# 03_ANALOG_A.net
KiCad netlist of a schematic drawn in Altium Designer
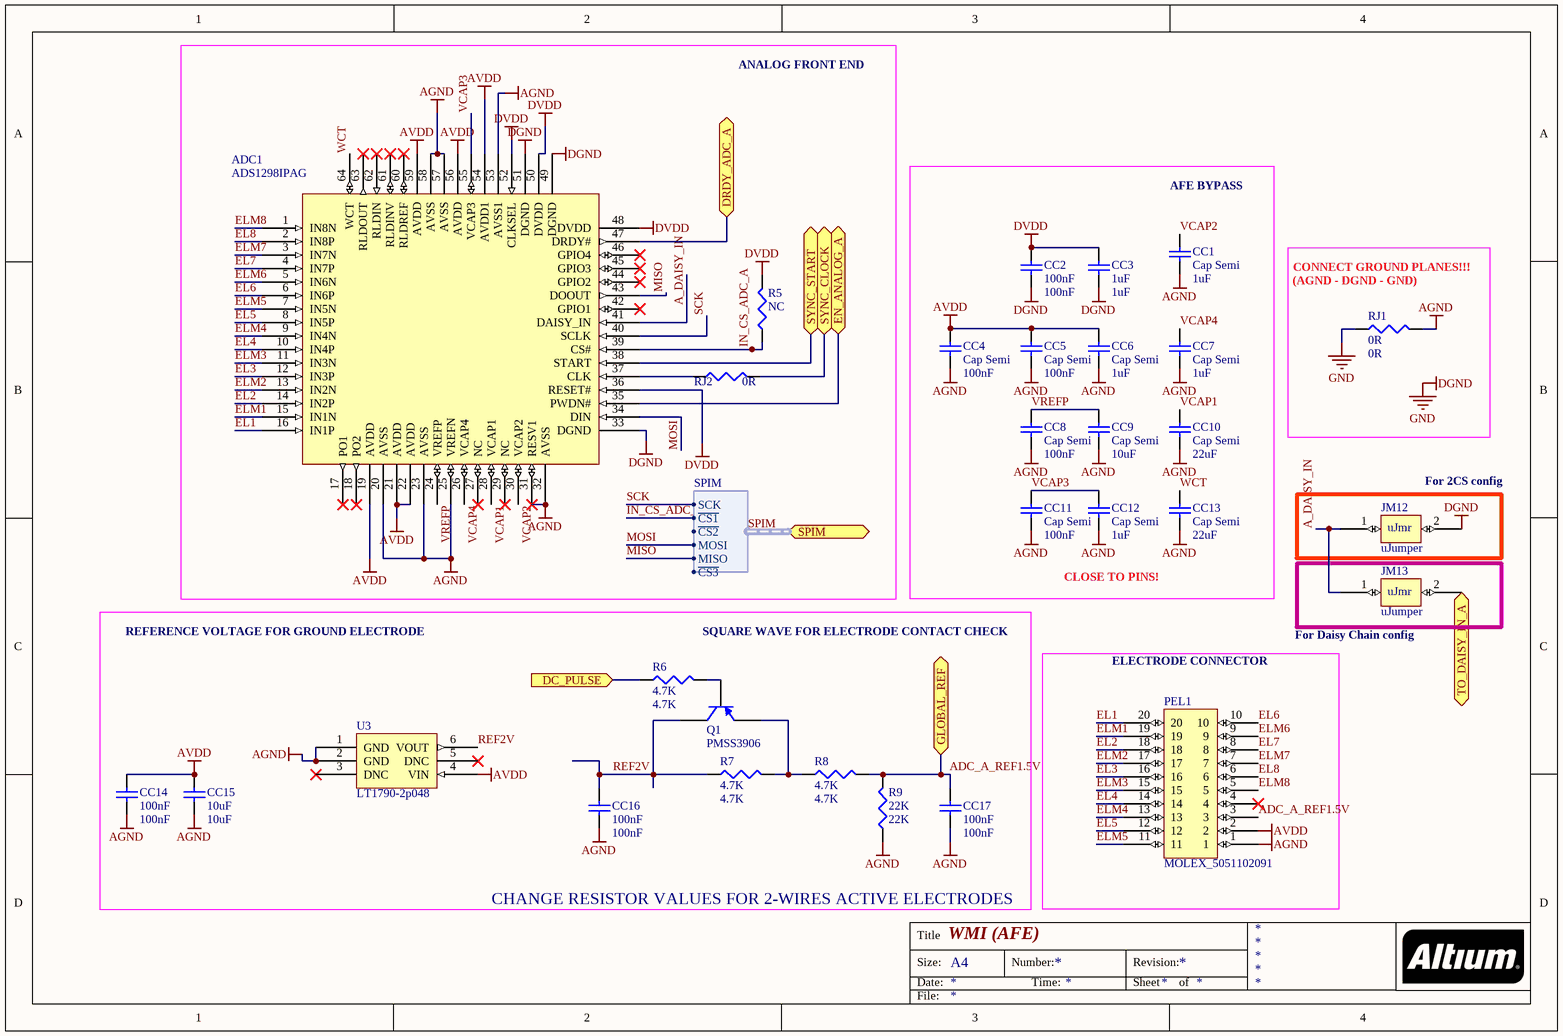
[diagram p0: 03_ANALOG_A.SchDoc]

(export (version "E")
  (design (tool "Eeschema 10.0.6"))
  (components
    (comp (ref "ADC1")
      (value "ADS1298IPAG")
      (footprint "Atmel Microcontroller 32-Bit ARM:LQFP64_M")
      (libsource (lib "Schlib1") (part "ADS1298"))
    )
    (comp (ref "CC1")
      (value "Cap Semi")
      (footprint "0402")
      (description "Capacitor (Semiconductor SIM Model)")
      (fields (field (name "ALTIUM_VALUE") "1uF") (field (name "PUBLISHER") "Altium Limited"))
      (libsource (lib "Miscellaneous Devices") (part "Cap Semi"))
    )
    (comp (ref "CC2")
      (value "100nF")
      (footprint "0402")
      (description "Capacitor (Semiconductor SIM Model)")
      (fields (field (name "ALTIUM_VALUE") "100nF") (field (name "PUBLISHER") "Altium Limited"))
      (libsource (lib "Miscellaneous Devices") (part "Cap Semi"))
    )
    (comp (ref "CC3")
      (value "1uF")
      (footprint "0402")
      (description "Capacitor (Semiconductor SIM Model)")
      (fields (field (name "ALTIUM_VALUE") "1uF") (field (name "PUBLISHER") "Altium Limited"))
      (libsource (lib "Miscellaneous Devices") (part "Cap Semi"))
    )
    (comp (ref "CC4")
      (value "Cap Semi")
      (footprint "0402")
      (description "Capacitor (Semiconductor SIM Model)")
      (fields (field (name "ALTIUM_VALUE") "100nF") (field (name "PUBLISHER") "Altium Limited"))
      (libsource (lib "Miscellaneous Devices") (part "Cap Semi"))
    )
    (comp (ref "CC5")
      (value "Cap Semi")
      (footprint "0402")
      (description "Capacitor (Semiconductor SIM Model)")
      (fields (field (name "ALTIUM_VALUE") "100nF") (field (name "PUBLISHER") "Altium Limited"))
      (libsource (lib "Miscellaneous Devices") (part "Cap Semi"))
    )
    (comp (ref "CC6")
      (value "Cap Semi")
      (footprint "0402")
      (description "Capacitor (Semiconductor SIM Model)")
      (fields (field (name "ALTIUM_VALUE") "1uF") (field (name "PUBLISHER") "Altium Limited"))
      (libsource (lib "Miscellaneous Devices") (part "Cap Semi"))
    )
    (comp (ref "CC7")
      (value "Cap Semi")
      (footprint "0402")
      (description "Capacitor (Semiconductor SIM Model)")
      (fields (field (name "ALTIUM_VALUE") "1uF") (field (name "PUBLISHER") "Altium Limited"))
      (libsource (lib "Miscellaneous Devices") (part "Cap Semi"))
    )
    (comp (ref "CC8")
      (value "Cap Semi")
      (footprint "0402")
      (description "Capacitor (Semiconductor SIM Model)")
      (fields (field (name "ALTIUM_VALUE") "100nF") (field (name "PUBLISHER") "Altium Limited"))
      (libsource (lib "Miscellaneous Devices") (part "Cap Semi"))
    )
    (comp (ref "CC9")
      (value "Cap Semi")
      (footprint "0402")
      (description "Capacitor (Semiconductor SIM Model)")
      (fields (field (name "ALTIUM_VALUE") "10uF") (field (name "PUBLISHER") "Altium Limited"))
      (libsource (lib "Miscellaneous Devices") (part "Cap Semi"))
    )
    (comp (ref "CC10")
      (value "Cap Semi")
      (footprint "J1-0603")
      (description "Capacitor (Semiconductor SIM Model)")
      (fields (field (name "ALTIUM_VALUE") "22uF") (field (name "PUBLISHER") "Altium Limited"))
      (libsource (lib "Miscellaneous Devices") (part "Cap Semi"))
    )
    (comp (ref "CC11")
      (value "Cap Semi")
      (footprint "0402")
      (description "Capacitor (Semiconductor SIM Model)")
      (fields (field (name "ALTIUM_VALUE") "100nF") (field (name "PUBLISHER") "Altium Limited"))
      (libsource (lib "Miscellaneous Devices") (part "Cap Semi"))
    )
    (comp (ref "CC12")
      (value "Cap Semi")
      (footprint "0402")
      (description "Capacitor (Semiconductor SIM Model)")
      (fields (field (name "ALTIUM_VALUE") "1uF") (field (name "PUBLISHER") "Altium Limited"))
      (libsource (lib "Miscellaneous Devices") (part "Cap Semi"))
    )
    (comp (ref "CC13")
      (value "Cap Semi")
      (footprint "1608[0603]")
      (description "Capacitor (Semiconductor SIM Model)")
      (fields (field (name "ALTIUM_VALUE") "22uF") (field (name "PUBLISHER") "Altium Limited"))
      (libsource (lib "Miscellaneous Devices") (part "Cap Semi"))
    )
    (comp (ref "CC14")
      (value "100nF")
      (footprint "0402")
      (description "Capacitor (Semiconductor SIM Model)")
      (fields (field (name "ALTIUM_VALUE") "100nF") (field (name "PUBLISHER") "Altium Limited"))
      (libsource (lib "Miscellaneous Devices") (part "Cap Semi"))
    )
    (comp (ref "CC15")
      (value "10uF")
      (footprint "0402")
      (description "Capacitor (Semiconductor SIM Model)")
      (fields (field (name "ALTIUM_VALUE") "10uF") (field (name "PUBLISHER") "Altium Limited"))
      (libsource (lib "Miscellaneous Devices") (part "Cap Semi"))
    )
    (comp (ref "CC16")
      (value "100nF")
      (footprint "0402")
      (description "Capacitor (Semiconductor SIM Model)")
      (fields (field (name "ALTIUM_VALUE") "100nF") (field (name "PUBLISHER") "Altium Limited"))
      (libsource (lib "Miscellaneous Devices") (part "Cap Semi"))
    )
    (comp (ref "CC17")
      (value "100nF")
      (footprint "0402")
      (description "Capacitor (Semiconductor SIM Model)")
      (fields (field (name "ALTIUM_VALUE") "100nF") (field (name "PUBLISHER") "Altium Limited"))
      (libsource (lib "Miscellaneous Devices") (part "Cap Semi"))
    )
    (comp (ref "JM12") (value "uJumper") (footprint "UJMPR") (libsource (lib "Schlib1") (part "uJumper")))
    (comp (ref "JM13") (value "uJumper") (footprint "UJMPR") (libsource (lib "Schlib1") (part "uJumper")))
    (comp (ref "PEL1")
      (value "MOLEX_5051102091")
      (footprint "MOLEX_5051102091")
      (libsource (lib "Schlib1") (part "MOLEX_5051102091"))
    )
    (comp (ref "Q1")
      (value "PMSS3906")
      (footprint "SOT323_N")
      (description "PNP Switching Transistor")
      (fields (field (name "PUBLISHER") "Altium Limited"))
      (libsource (lib "Philips Discrete BJT - Low Power") (part "PMSS3906"))
    )
    (comp (ref "R5")
      (value "NC")
      (footprint "0402")
      (description "Resistor")
      (fields (field (name "PUBLISHER") "Altium Limited"))
      (libsource (lib "Miscellaneous Devices") (part "Res3"))
    )
    (comp (ref "R6")
      (value "4.7K")
      (footprint "0402")
      (description "Resistor")
      (fields (field (name "ALTIUM_VALUE") "4.7K") (field (name "PUBLISHER") "Altium Limited"))
      (libsource (lib "Miscellaneous Devices") (part "Res3"))
    )
    (comp (ref "R7")
      (value "4.7K")
      (footprint "0402")
      (description "Resistor")
      (fields (field (name "ALTIUM_VALUE") "4.7K") (field (name "PUBLISHER") "Altium Limited"))
      (libsource (lib "Miscellaneous Devices") (part "Res3"))
    )
    (comp (ref "R8")
      (value "4.7K")
      (footprint "0402")
      (description "Resistor")
      (fields (field (name "ALTIUM_VALUE") "4.7K") (field (name "PUBLISHER") "Altium Limited"))
      (libsource (lib "Miscellaneous Devices") (part "Res3"))
    )
    (comp (ref "R9")
      (value "22K")
      (footprint "0402")
      (description "Resistor")
      (fields (field (name "ALTIUM_VALUE") "22K") (field (name "PUBLISHER") "Altium Limited"))
      (libsource (lib "Miscellaneous Devices") (part "Res3"))
    )
    (comp (ref "RJ1")
      (value "0R")
      (footprint "0402")
      (description "Resistor")
      (fields (field (name "ALTIUM_VALUE") "0R") (field (name "PUBLISHER") "Altium Limited"))
      (libsource (lib "Miscellaneous Devices") (part "Res3"))
    )
    (comp (ref "RJ2")
      (value "0R")
      (footprint "0402")
      (description "Resistor")
      (fields (field (name "PUBLISHER") "Altium Limited"))
      (libsource (lib "Miscellaneous Devices") (part "Res3"))
    )
    (comp (ref "U3")
      (value "LT1790-2p048")
      (footprint "SOT-23_A_N")
      (libsource (lib "Schlib1") (part "LT1790"))
    )
  )
  (nets
    (net (code "2") (name "/ADC_A_REF1.5V") (class "Default")
      (node (ref "CC17") (pin "2") (pinfunction "2_2") (pintype "passive"))
      (node (ref "PEL1") (pin "3") (pinfunction "3_3") (pintype "bidirectional"))
      (node (ref "R8") (pin "2") (pinfunction "2_2") (pintype "passive"))
      (node (ref "R9") (pin "2") (pinfunction "2_2") (pintype "passive"))
    )
    (net (code "3") (name "/A_DAISY_IN") (class "Default")
      (node (ref "ADC1") (pin "41") (pinfunction "DAISY_IN_41") (pintype "input"))
      (node (ref "JM12") (pin "1") (pintype "bidirectional"))
      (node (ref "JM13") (pin "1") (pintype "bidirectional"))
    )
    (net (code "4") (name "/DC_PULSE") (class "Default")
      (node (ref "R6") (pin "1") (pinfunction "1_1") (pintype "passive"))
    )
    (net (code "5") (name "/DRDY_ADC_A") (class "Default")
      (node (ref "ADC1") (pin "47") (pinfunction "DRDY#_47") (pintype "output"))
    )
    (net (code "6") (name "/EL1") (class "Default")
      (node (ref "ADC1") (pin "16") (pinfunction "IN1P_16") (pintype "input"))
      (node (ref "PEL1") (pin "20") (pinfunction "20_20") (pintype "bidirectional"))
    )
    (net (code "7") (name "/EL2") (class "Default")
      (node (ref "ADC1") (pin "14") (pinfunction "IN2P_14") (pintype "input"))
      (node (ref "PEL1") (pin "18") (pinfunction "18_18") (pintype "bidirectional"))
    )
    (net (code "8") (name "/EL3") (class "Default")
      (node (ref "ADC1") (pin "12") (pinfunction "IN3P_12") (pintype "input"))
      (node (ref "PEL1") (pin "16") (pinfunction "16_16") (pintype "bidirectional"))
    )
    (net (code "9") (name "/EL4") (class "Default")
      (node (ref "ADC1") (pin "10") (pinfunction "IN4P_10") (pintype "input"))
      (node (ref "PEL1") (pin "14") (pinfunction "14_14") (pintype "bidirectional"))
    )
    (net (code "10") (name "/EL5") (class "Default")
      (node (ref "ADC1") (pin "8") (pinfunction "IN5P_8") (pintype "input"))
      (node (ref "PEL1") (pin "12") (pinfunction "12_12") (pintype "bidirectional"))
    )
    (net (code "11") (name "/EL6") (class "Default")
      (node (ref "ADC1") (pin "6") (pinfunction "IN6P_6") (pintype "input"))
      (node (ref "PEL1") (pin "10") (pinfunction "10_10") (pintype "bidirectional"))
    )
    (net (code "12") (name "/EL7") (class "Default")
      (node (ref "ADC1") (pin "4") (pinfunction "IN7P_4") (pintype "input"))
      (node (ref "PEL1") (pin "8") (pinfunction "8_8") (pintype "bidirectional"))
    )
    (net (code "13") (name "/EL8") (class "Default")
      (node (ref "ADC1") (pin "2") (pinfunction "IN8P_2") (pintype "input"))
      (node (ref "PEL1") (pin "6") (pinfunction "6_6") (pintype "bidirectional"))
    )
    (net (code "14") (name "/ELM1") (class "Default")
      (node (ref "ADC1") (pin "15") (pinfunction "IN1N_15") (pintype "input"))
      (node (ref "PEL1") (pin "19") (pinfunction "19_19") (pintype "bidirectional"))
    )
    (net (code "15") (name "/ELM2") (class "Default")
      (node (ref "ADC1") (pin "13") (pinfunction "IN2N_13") (pintype "input"))
      (node (ref "PEL1") (pin "17") (pinfunction "17_17") (pintype "bidirectional"))
    )
    (net (code "16") (name "/ELM3") (class "Default")
      (node (ref "ADC1") (pin "11") (pinfunction "IN3N_11") (pintype "input"))
      (node (ref "PEL1") (pin "15") (pinfunction "15_15") (pintype "bidirectional"))
    )
    (net (code "17") (name "/ELM4") (class "Default")
      (node (ref "ADC1") (pin "9") (pinfunction "IN4N_9") (pintype "input"))
      (node (ref "PEL1") (pin "13") (pinfunction "13_13") (pintype "bidirectional"))
    )
    (net (code "18") (name "/ELM5") (class "Default")
      (node (ref "ADC1") (pin "7") (pinfunction "IN5N_7") (pintype "input"))
      (node (ref "PEL1") (pin "11") (pinfunction "11_11") (pintype "bidirectional"))
    )
    (net (code "19") (name "/ELM6") (class "Default")
      (node (ref "ADC1") (pin "5") (pinfunction "IN6N_5") (pintype "input"))
      (node (ref "PEL1") (pin "9") (pinfunction "9_9") (pintype "bidirectional"))
    )
    (net (code "20") (name "/ELM7") (class "Default")
      (node (ref "ADC1") (pin "3") (pinfunction "IN7N_3") (pintype "input"))
      (node (ref "PEL1") (pin "7") (pinfunction "7_7") (pintype "bidirectional"))
    )
    (net (code "21") (name "/ELM8") (class "Default")
      (node (ref "ADC1") (pin "1") (pinfunction "IN8N_1") (pintype "input"))
      (node (ref "PEL1") (pin "5") (pinfunction "5_5") (pintype "bidirectional"))
    )
    (net (code "22") (name "/EN_ANALOG_A") (class "Default")
      (node (ref "ADC1") (pin "35") (pinfunction "PWDN#_35") (pintype "input"))
    )
    (net (code "23") (name "/IN_CS_ADC_A") (class "Default")
      (node (ref "ADC1") (pin "39") (pinfunction "CS#_39") (pintype "input"))
      (node (ref "R5") (pin "1") (pinfunction "1_1") (pintype "passive"))
    )
    (net (code "24") (name "/MISO") (class "Default")
      (node (ref "ADC1") (pin "43") (pinfunction "DOOUT_43") (pintype "output"))
    )
    (net (code "25") (name "/MOSI") (class "Default")
      (node (ref "ADC1") (pin "34") (pinfunction "DIN_34") (pintype "input"))
    )
    (net (code "26") (name "/REF2V") (class "Default")
      (node (ref "CC16") (pin "2") (pinfunction "2_2") (pintype "passive"))
      (node (ref "Q1") (pin "3") (pinfunction "C_3") (pintype "passive"))
      (node (ref "R7") (pin "1") (pinfunction "1_1") (pintype "passive"))
      (node (ref "U3") (pin "6") (pinfunction "VOUT_6") (pintype "output"))
    )
    (net (code "27") (name "/SCK") (class "Default")
      (node (ref "ADC1") (pin "40") (pinfunction "SCLK_40") (pintype "input"))
    )
    (net (code "29") (name "/SYNC_CLOCK") (class "Default")
      (node (ref "RJ2") (pin "2") (pinfunction "2_2") (pintype "passive"))
    )
    (net (code "30") (name "/SYNC_START") (class "Default")
      (node (ref "ADC1") (pin "38") (pinfunction "START_38") (pintype "input"))
    )
    (net (code "31") (name "/TO_DAISY_IN_A") (class "Default")
      (node (ref "JM13") (pin "2") (pintype "bidirectional"))
    )
    (net (code "32") (name "/VCAP1") (class "Default")
      (node (ref "ADC1") (pin "28") (pinfunction "VCAP1_28") (pintype "bidirectional"))
      (node (ref "CC10") (pin "2") (pinfunction "2_2") (pintype "passive"))
    )
    (net (code "33") (name "/VCAP2") (class "Default")
      (node (ref "ADC1") (pin "30") (pinfunction "VCAP2_30") (pintype "bidirectional"))
      (node (ref "CC1") (pin "2") (pinfunction "2_2") (pintype "passive"))
    )
    (net (code "34") (name "/VCAP3") (class "Default")
      (node (ref "ADC1") (pin "55") (pinfunction "VCAP3_55") (pintype "bidirectional"))
      (node (ref "CC11") (pin "2") (pinfunction "2_2") (pintype "passive"))
      (node (ref "CC12") (pin "2") (pinfunction "2_2") (pintype "passive"))
    )
    (net (code "35") (name "/VCAP4") (class "Default")
      (node (ref "ADC1") (pin "26") (pinfunction "VCAP4_26") (pintype "bidirectional"))
      (node (ref "CC7") (pin "2") (pinfunction "2_2") (pintype "passive"))
    )
    (net (code "36") (name "/VREFP") (class "Default")
      (node (ref "ADC1") (pin "24") (pinfunction "VREFP_24") (pintype "bidirectional"))
      (node (ref "CC8") (pin "2") (pinfunction "2_2") (pintype "passive"))
      (node (ref "CC9") (pin "2") (pinfunction "2_2") (pintype "passive"))
    )
    (net (code "37") (name "/WCT") (class "Default")
      (node (ref "ADC1") (pin "64") (pinfunction "WCT_64") (pintype "bidirectional"))
      (node (ref "CC13") (pin "2") (pinfunction "2_2") (pintype "passive"))
    )
    (net (code "38") (name "AGND") (class "Default")
      (node (ref "ADC1") (pin "20") (pinfunction "AVSS_20") (pintype "power_in"))
      (node (ref "ADC1") (pin "23") (pinfunction "AVSS_23") (pintype "power_in"))
      (node (ref "ADC1") (pin "25") (pinfunction "VREFN_25") (pintype "bidirectional"))
      (node (ref "ADC1") (pin "31") (pinfunction "RESV1_31") (pintype "bidirectional"))
      (node (ref "ADC1") (pin "32") (pinfunction "AVSS_32") (pintype "power_in"))
      (node (ref "ADC1") (pin "53") (pinfunction "AVSS1_53") (pintype "power_in"))
      (node (ref "ADC1") (pin "57") (pinfunction "AVSS_57") (pintype "power_in"))
      (node (ref "ADC1") (pin "58") (pinfunction "AVSS_58") (pintype "power_in"))
      (node (ref "CC1") (pin "1") (pinfunction "1_1") (pintype "passive"))
      (node (ref "CC10") (pin "1") (pinfunction "1_1") (pintype "passive"))
      (node (ref "CC11") (pin "1") (pinfunction "1_1") (pintype "passive"))
      (node (ref "CC12") (pin "1") (pinfunction "1_1") (pintype "passive"))
      (node (ref "CC13") (pin "1") (pinfunction "1_1") (pintype "passive"))
      (node (ref "CC14") (pin "1") (pinfunction "1_1") (pintype "passive"))
      (node (ref "CC15") (pin "1") (pinfunction "1_1") (pintype "passive"))
      (node (ref "CC16") (pin "1") (pinfunction "1_1") (pintype "passive"))
      (node (ref "CC17") (pin "1") (pinfunction "1_1") (pintype "passive"))
      (node (ref "CC4") (pin "1") (pinfunction "1_1") (pintype "passive"))
      (node (ref "CC5") (pin "1") (pinfunction "1_1") (pintype "passive"))
      (node (ref "CC6") (pin "1") (pinfunction "1_1") (pintype "passive"))
      (node (ref "CC7") (pin "1") (pinfunction "1_1") (pintype "passive"))
      (node (ref "CC8") (pin "1") (pinfunction "1_1") (pintype "passive"))
      (node (ref "CC9") (pin "1") (pinfunction "1_1") (pintype "passive"))
      (node (ref "PEL1") (pin "1") (pinfunction "1_1") (pintype "bidirectional"))
      (node (ref "R9") (pin "1") (pinfunction "1_1") (pintype "passive"))
      (node (ref "RJ1") (pin "2") (pinfunction "2_2") (pintype "passive"))
      (node (ref "U3") (pin "1") (pinfunction "GND_1") (pintype "power_in"))
      (node (ref "U3") (pin "2") (pinfunction "GND_2") (pintype "power_in"))
    )
    (net (code "39") (name "AVDD") (class "Default")
      (node (ref "ADC1") (pin "19") (pinfunction "AVDD_19") (pintype "power_in"))
      (node (ref "ADC1") (pin "21") (pinfunction "AVDD_21") (pintype "power_in"))
      (node (ref "ADC1") (pin "22") (pinfunction "AVDD_22") (pintype "power_in"))
      (node (ref "ADC1") (pin "54") (pinfunction "AVDD1_54") (pintype "power_in"))
      (node (ref "ADC1") (pin "56") (pinfunction "AVDD_56") (pintype "power_in"))
      (node (ref "ADC1") (pin "59") (pinfunction "AVDD_59") (pintype "power_in"))
      (node (ref "CC14") (pin "2") (pinfunction "2_2") (pintype "passive"))
      (node (ref "CC15") (pin "2") (pinfunction "2_2") (pintype "passive"))
      (node (ref "CC4") (pin "2") (pinfunction "2_2") (pintype "passive"))
      (node (ref "CC5") (pin "2") (pinfunction "2_2") (pintype "passive"))
      (node (ref "CC6") (pin "2") (pinfunction "2_2") (pintype "passive"))
      (node (ref "PEL1") (pin "2") (pinfunction "2_2") (pintype "bidirectional"))
      (node (ref "U3") (pin "4") (pinfunction "VIN_4") (pintype "input"))
    )
    (net (code "40") (name "DGND") (class "Default")
      (node (ref "ADC1") (pin "33") (pinfunction "DGND_33") (pintype "power_in"))
      (node (ref "ADC1") (pin "49") (pinfunction "DGND_49") (pintype "power_in"))
      (node (ref "ADC1") (pin "51") (pinfunction "DGND_51") (pintype "power_in"))
      (node (ref "CC2") (pin "1") (pinfunction "1_1") (pintype "passive"))
      (node (ref "CC3") (pin "1") (pinfunction "1_1") (pintype "passive"))
      (node (ref "JM12") (pin "2") (pintype "bidirectional"))
      (node (ref "RJ1") (pin "1") (pinfunction "1_1") (pintype "passive"))
    )
    (net (code "41") (name "DVDD") (class "Default")
      (node (ref "ADC1") (pin "36") (pinfunction "RESET#_36") (pintype "input"))
      (node (ref "ADC1") (pin "48") (pinfunction "DVDD_48") (pintype "power_in"))
      (node (ref "ADC1") (pin "50") (pinfunction "DVDD_50") (pintype "power_in"))
      (node (ref "ADC1") (pin "52") (pinfunction "CLKSEL_52") (pintype "input"))
      (node (ref "CC2") (pin "2") (pinfunction "2_2") (pintype "passive"))
      (node (ref "CC3") (pin "2") (pinfunction "2_2") (pintype "passive"))
      (node (ref "R5") (pin "2") (pinfunction "2_2") (pintype "passive"))
    )
    (net (code "42") (name "Net-(ADC1-CLK)") (class "Default")
      (node (ref "ADC1") (pin "37") (pinfunction "CLK_37") (pintype "input"))
      (node (ref "RJ2") (pin "1") (pinfunction "1_1") (pintype "passive"))
    )
    (net (code "43") (name "Net-(Q1-B)") (class "Default")
      (node (ref "Q1") (pin "1") (pinfunction "B_1") (pintype "passive"))
      (node (ref "R6") (pin "2") (pinfunction "2_2") (pintype "passive"))
    )
    (net (code "44") (name "Net-(Q1-E)") (class "Default")
      (node (ref "Q1") (pin "2") (pinfunction "E_2") (pintype "passive"))
      (node (ref "R7") (pin "2") (pinfunction "2_2") (pintype "passive"))
      (node (ref "R8") (pin "1") (pinfunction "1_1") (pintype "passive"))
    )
    (net (code "45") (name "unconnected-(ADC1-GPIO1-Pad42)") (class "Default")
      (node (ref "ADC1") (pin "42") (pinfunction "GPIO1_42") (pintype "bidirectional+no_connect"))
    )
    (net (code "46") (name "unconnected-(ADC1-GPIO2-Pad44)") (class "Default")
      (node (ref "ADC1") (pin "44") (pinfunction "GPIO2_44") (pintype "bidirectional+no_connect"))
    )
    (net (code "47") (name "unconnected-(ADC1-GPIO3-Pad45)") (class "Default")
      (node (ref "ADC1") (pin "45") (pinfunction "GPIO3_45") (pintype "bidirectional+no_connect"))
    )
    (net (code "48") (name "unconnected-(ADC1-GPIO4-Pad46)") (class "Default")
      (node (ref "ADC1") (pin "46") (pinfunction "GPIO4_46") (pintype "bidirectional+no_connect"))
    )
    (net (code "49") (name "unconnected-(ADC1-NC-Pad27)") (class "Default")
      (node (ref "ADC1") (pin "27") (pinfunction "NC_27") (pintype "bidirectional+no_connect"))
    )
    (net (code "50") (name "unconnected-(ADC1-NC-Pad29)") (class "Default")
      (node (ref "ADC1") (pin "29") (pinfunction "NC_29") (pintype "bidirectional+no_connect"))
    )
    (net (code "51") (name "unconnected-(ADC1-PO1-Pad17)") (class "Default")
      (node (ref "ADC1") (pin "17") (pinfunction "PO1_17") (pintype "output+no_connect"))
    )
    (net (code "52") (name "unconnected-(ADC1-PO2-Pad18)") (class "Default")
      (node (ref "ADC1") (pin "18") (pinfunction "PO2_18") (pintype "output+no_connect"))
    )
    (net (code "53") (name "unconnected-(ADC1-RLDIN-Pad62)") (class "Default")
      (node (ref "ADC1") (pin "62") (pinfunction "RLDIN_62") (pintype "input+no_connect"))
    )
    (net (code "54") (name "unconnected-(ADC1-RLDINV-Pad61)") (class "Default")
      (node (ref "ADC1") (pin "61") (pinfunction "RLDINV_61") (pintype "bidirectional+no_connect"))
    )
    (net (code "55") (name "unconnected-(ADC1-RLDOUT-Pad63)") (class "Default")
      (node (ref "ADC1") (pin "63") (pinfunction "RLDOUT_63") (pintype "output+no_connect"))
    )
    (net (code "56") (name "unconnected-(ADC1-RLDREF-Pad60)") (class "Default")
      (node (ref "ADC1") (pin "60") (pinfunction "RLDREF_60") (pintype "bidirectional+no_connect"))
    )
    (net (code "57") (name "unconnected-(PEL1-Pad4)") (class "Default")
      (node (ref "PEL1") (pin "4") (pinfunction "4_4") (pintype "bidirectional+no_connect"))
    )
    (net (code "58") (name "unconnected-(U3-DNC-Pad3)") (class "Default")
      (node (ref "U3") (pin "3") (pinfunction "DNC_3") (pintype "passive+no_connect"))
    )
    (net (code "59") (name "unconnected-(U3-DNC-Pad5)") (class "Default")
      (node (ref "U3") (pin "5") (pinfunction "DNC_5") (pintype "passive+no_connect"))
    )
  )
)
